# headphone_amp_smd.net
KiCad netlist of a schematic drawn in EAGLE
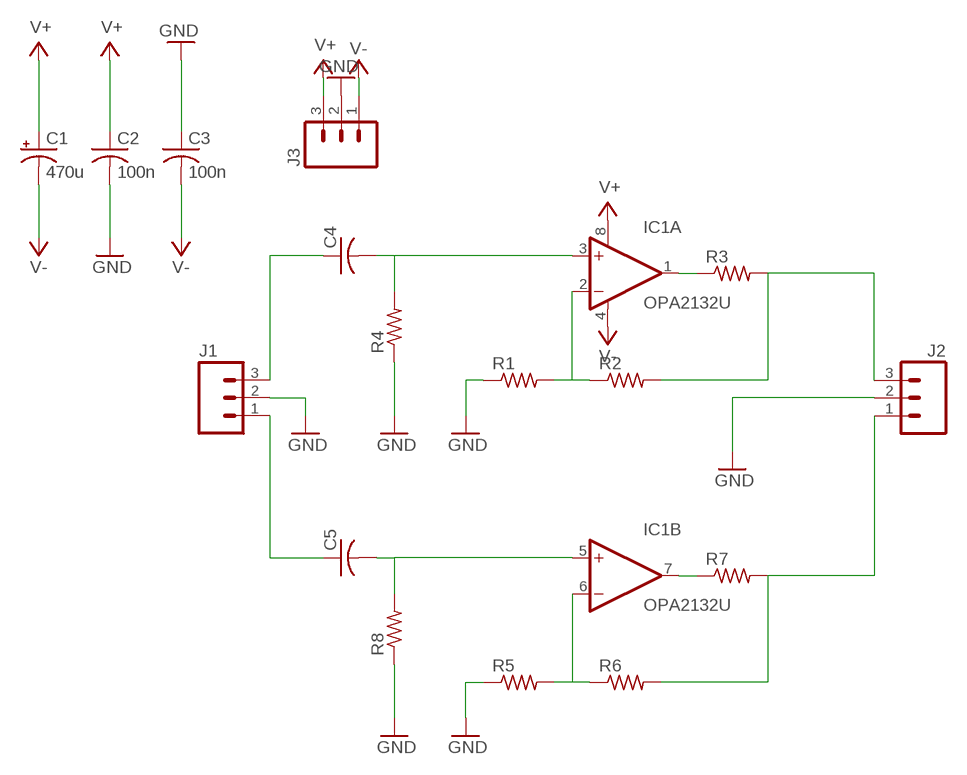
[diagram p0: schematic, sheet 1]

(export (version "E")
  (design (tool "Eeschema 10.0.6"))
  (components
    (comp (ref "C1")
      (value "470u")
      (footprint "eagle-import:E5-10,5")
      (libsource (lib "eagle-import") (part "CPOL-USE5-10.5"))
    )
    (comp (ref "C2")
      (value "100n")
      (footprint "eagle-import:C0805K")
      (libsource (lib "eagle-import") (part "C-USC0805K"))
    )
    (comp (ref "C3")
      (value "100n")
      (footprint "eagle-import:C0805K")
      (libsource (lib "eagle-import") (part "C-USC0805K"))
    )
    (comp (ref "C4")
      (value "C-US025_050-035X075")
      (footprint "eagle-import:C025_050-035X075")
      (libsource (lib "eagle-import") (part "C-US025_050-035X075"))
    )
    (comp (ref "C5")
      (value "C-US025_050-035X075")
      (footprint "eagle-import:C025_050-035X075")
      (libsource (lib "eagle-import") (part "C-US025_050-035X075"))
    )
    (comp (ref "IC1")
      (value "OPA2132U")
      (footprint "eagle-import:SO08")
      (fields (field (name "MF") "TEXAS INSTRUMENTS"))
      (libsource (lib "eagle-import") (part "OPA2132U"))
    )
    (comp (ref "J1")
      (value "M03PTH")
      (footprint "eagle-import:1X03")
      (libsource (lib "eagle-import") (part "M03PTH"))
    )
    (comp (ref "J2")
      (value "M03PTH")
      (footprint "eagle-import:1X03")
      (libsource (lib "eagle-import") (part "M03PTH"))
    )
    (comp (ref "J3")
      (value "M03PTH")
      (footprint "eagle-import:1X03")
      (libsource (lib "eagle-import") (part "M03PTH"))
    )
    (comp (ref "R1")
      (value "R-US_R1206")
      (footprint "eagle-import:R1206")
      (libsource (lib "eagle-import") (part "R-US_R1206"))
    )
    (comp (ref "R2")
      (value "R-US_R1206")
      (footprint "eagle-import:R1206")
      (libsource (lib "eagle-import") (part "R-US_R1206"))
    )
    (comp (ref "R3")
      (value "R-US_R1206")
      (footprint "eagle-import:R1206")
      (libsource (lib "eagle-import") (part "R-US_R1206"))
    )
    (comp (ref "R4")
      (value "R-US_R1206")
      (footprint "eagle-import:R1206")
      (libsource (lib "eagle-import") (part "R-US_R1206"))
    )
    (comp (ref "R5")
      (value "R-US_R1206")
      (footprint "eagle-import:R1206")
      (libsource (lib "eagle-import") (part "R-US_R1206"))
    )
    (comp (ref "R6")
      (value "R-US_R1206")
      (footprint "eagle-import:R1206")
      (libsource (lib "eagle-import") (part "R-US_R1206"))
    )
    (comp (ref "R7")
      (value "R-US_R1206")
      (footprint "eagle-import:R1206")
      (libsource (lib "eagle-import") (part "R-US_R1206"))
    )
    (comp (ref "R8")
      (value "R-US_R1206")
      (footprint "eagle-import:R1206")
      (libsource (lib "eagle-import") (part "R-US_R1206"))
    )
  )
  (nets
    (net (code "1") (name "GND") (class "Default")
      (node (ref "C2") (pin "2") (pinfunction "2_2") (pintype "passive"))
      (node (ref "C3") (pin "1") (pinfunction "1_1") (pintype "passive"))
      (node (ref "J1") (pin "2") (pinfunction "2_2") (pintype "passive"))
      (node (ref "J2") (pin "2") (pinfunction "2_2") (pintype "passive"))
      (node (ref "J3") (pin "2") (pinfunction "2_2") (pintype "passive"))
      (node (ref "R1") (pin "1") (pinfunction "1_1") (pintype "passive"))
      (node (ref "R4") (pin "1") (pinfunction "1_1") (pintype "passive"))
      (node (ref "R5") (pin "1") (pinfunction "1_1") (pintype "passive"))
      (node (ref "R8") (pin "1") (pinfunction "1_1") (pintype "passive"))
    )
    (net (code "2") (name "Net-(C4-Pad1)") (class "Default")
      (node (ref "C4") (pin "1") (pinfunction "1_1") (pintype "passive"))
      (node (ref "J1") (pin "3") (pinfunction "3_3") (pintype "passive"))
    )
    (net (code "3") (name "Net-(C5-Pad1)") (class "Default")
      (node (ref "C5") (pin "1") (pinfunction "1_1") (pintype "passive"))
      (node (ref "J1") (pin "1") (pinfunction "1_1") (pintype "passive"))
    )
    (net (code "4") (name "Net-(IC1A-+IN)") (class "Default")
      (node (ref "C4") (pin "2") (pinfunction "2_2") (pintype "passive"))
      (node (ref "IC1") (pin "3") (pinfunction "+IN_3") (pintype "input"))
      (node (ref "R4") (pin "2") (pinfunction "2_2") (pintype "passive"))
    )
    (net (code "5") (name "Net-(IC1A--IN)") (class "Default")
      (node (ref "IC1") (pin "2") (pinfunction "-IN_2") (pintype "input"))
      (node (ref "R1") (pin "2") (pinfunction "2_2") (pintype "passive"))
      (node (ref "R2") (pin "1") (pinfunction "1_1") (pintype "passive"))
    )
    (net (code "6") (name "Net-(IC1A-OUT)") (class "Default")
      (node (ref "IC1") (pin "1") (pinfunction "OUT_1") (pintype "output"))
      (node (ref "R3") (pin "1") (pinfunction "1_1") (pintype "passive"))
    )
    (net (code "7") (name "Net-(IC1B-+IN)") (class "Default")
      (node (ref "C5") (pin "2") (pinfunction "2_2") (pintype "passive"))
      (node (ref "IC1") (pin "5") (pinfunction "+IN_5") (pintype "input"))
      (node (ref "R8") (pin "2") (pinfunction "2_2") (pintype "passive"))
    )
    (net (code "8") (name "Net-(IC1B--IN)") (class "Default")
      (node (ref "IC1") (pin "6") (pinfunction "-IN_6") (pintype "input"))
      (node (ref "R5") (pin "2") (pinfunction "2_2") (pintype "passive"))
      (node (ref "R6") (pin "1") (pinfunction "1_1") (pintype "passive"))
    )
    (net (code "9") (name "Net-(IC1B-OUT)") (class "Default")
      (node (ref "IC1") (pin "7") (pinfunction "OUT_7") (pintype "output"))
      (node (ref "R7") (pin "1") (pinfunction "1_1") (pintype "passive"))
    )
    (net (code "10") (name "Net-(J2-Pad1)") (class "Default")
      (node (ref "J2") (pin "1") (pinfunction "1_1") (pintype "passive"))
      (node (ref "R6") (pin "2") (pinfunction "2_2") (pintype "passive"))
      (node (ref "R7") (pin "2") (pinfunction "2_2") (pintype "passive"))
    )
    (net (code "11") (name "Net-(J2-Pad3)") (class "Default")
      (node (ref "J2") (pin "3") (pinfunction "3_3") (pintype "passive"))
      (node (ref "R2") (pin "2") (pinfunction "2_2") (pintype "passive"))
      (node (ref "R3") (pin "2") (pinfunction "2_2") (pintype "passive"))
    )
    (net (code "12") (name "V+") (class "Default")
      (node (ref "C1") (pin "+") (pinfunction "+_+") (pintype "passive"))
      (node (ref "C2") (pin "1") (pinfunction "1_1") (pintype "passive"))
      (node (ref "IC1") (pin "8") (pinfunction "V+_8") (pintype "power_in"))
      (node (ref "J3") (pin "3") (pinfunction "3_3") (pintype "passive"))
    )
    (net (code "13") (name "V-") (class "Default")
      (node (ref "C1") (pin "-") (pinfunction "-_-") (pintype "passive"))
      (node (ref "C3") (pin "2") (pinfunction "2_2") (pintype "passive"))
      (node (ref "IC1") (pin "4") (pinfunction "V-_4") (pintype "power_in"))
      (node (ref "J3") (pin "1") (pinfunction "1_1") (pintype "passive"))
    )
  )
)
